# USB_Audio_for_Switch.net
KiCad netlist of a schematic drawn in EAGLE
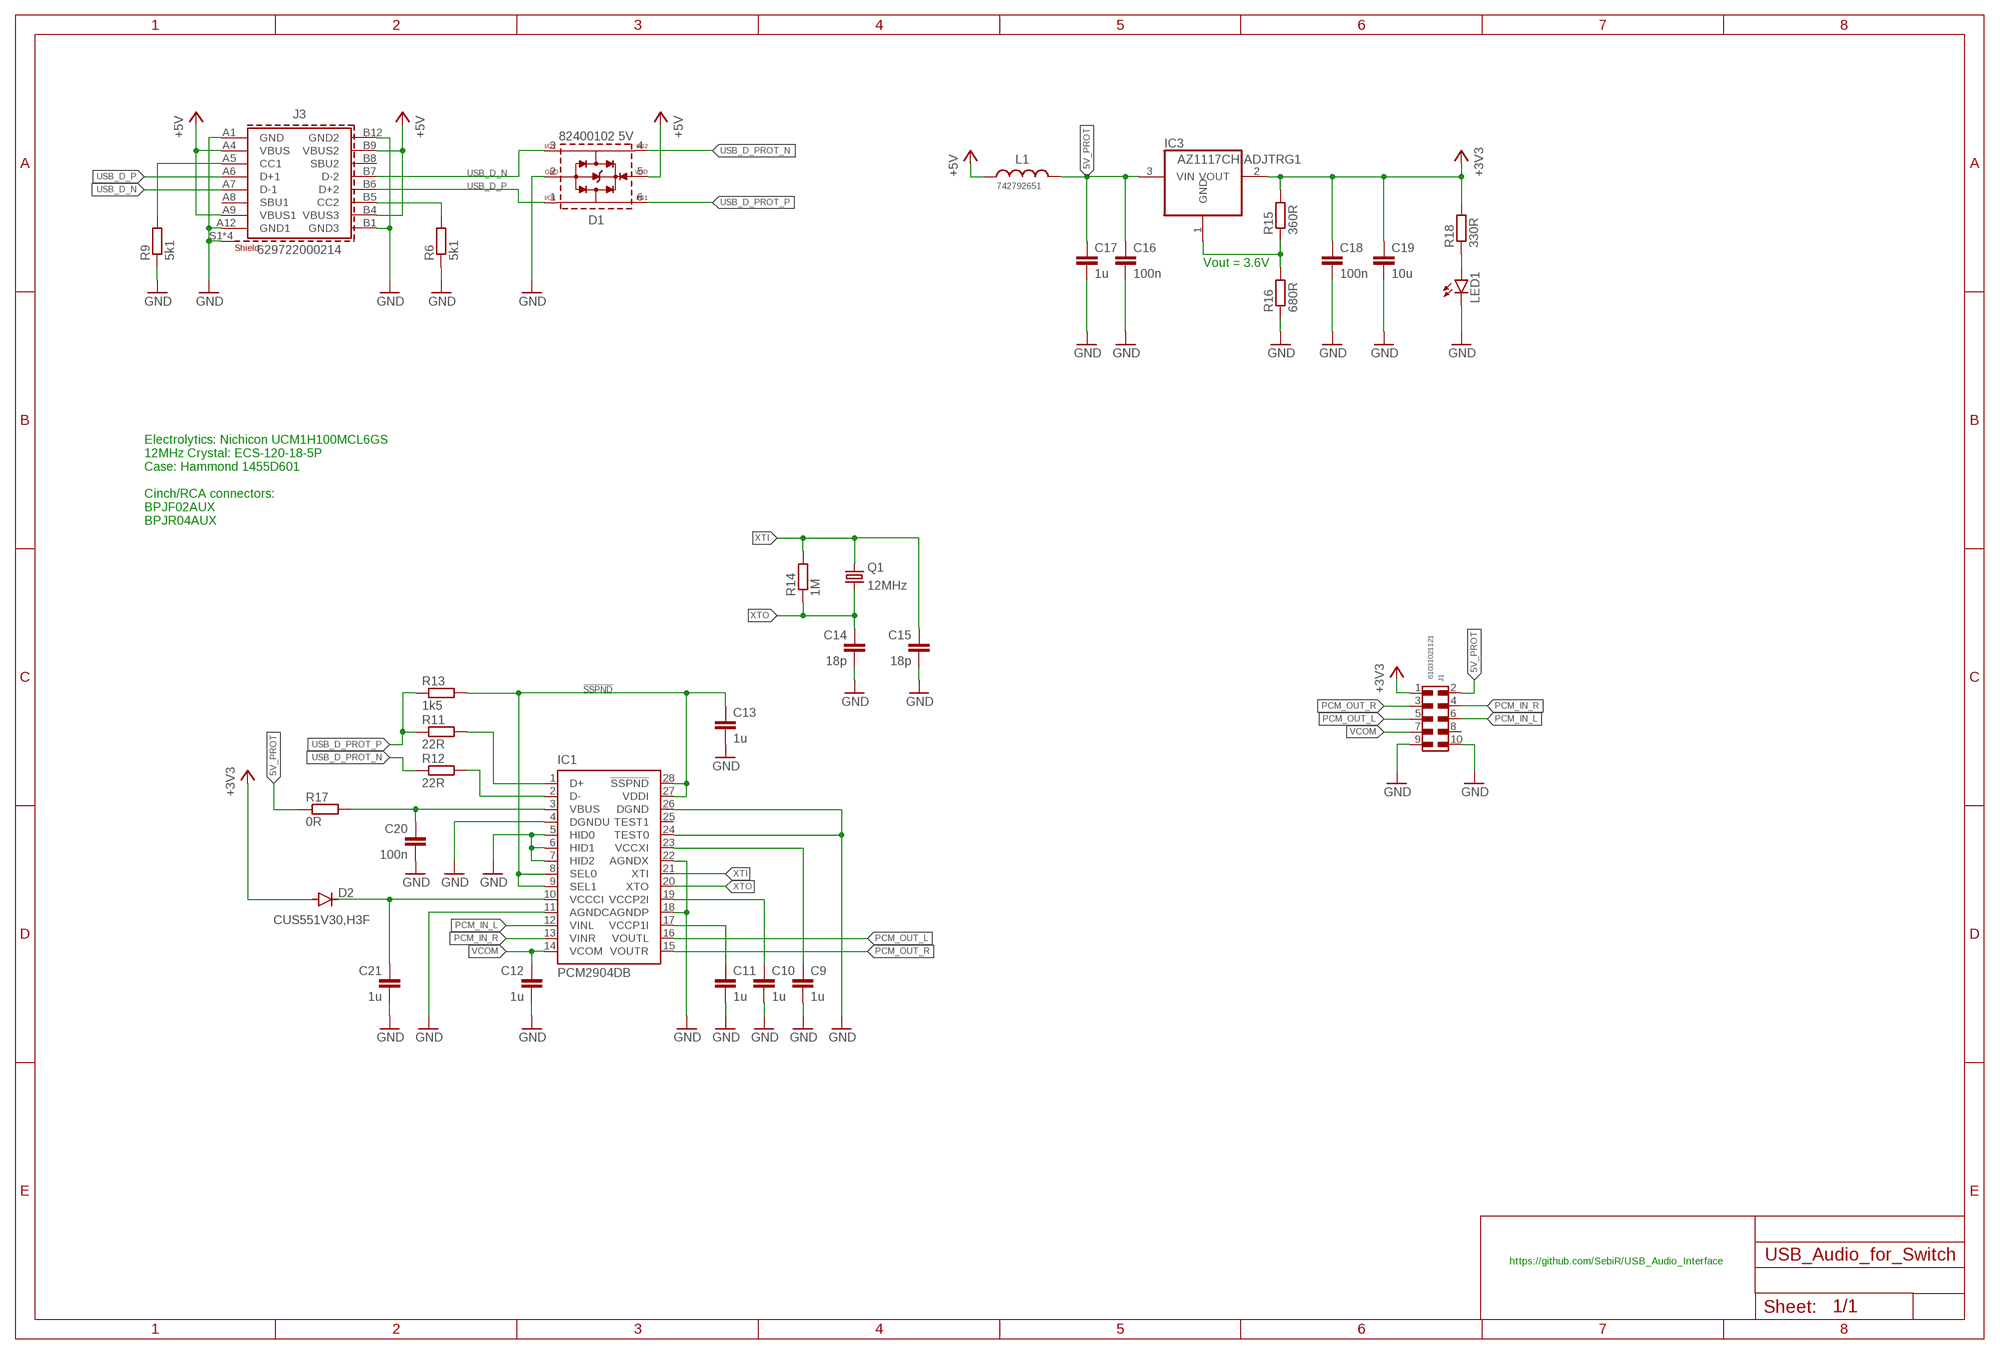
[diagram p0: schematic, sheet 1]

(export (version "E")
  (design (tool "Eeschema 10.0.6"))
  (components
    (comp (ref "C9")
      (value "1u")
      (footprint "eagle-import:C0603")
      (libsource (lib "eagle-import") (part "C-EUC0603"))
    )
    (comp (ref "C10")
      (value "1u")
      (footprint "eagle-import:C0603")
      (libsource (lib "eagle-import") (part "C-EUC0603"))
    )
    (comp (ref "C11")
      (value "1u")
      (footprint "eagle-import:C0603")
      (libsource (lib "eagle-import") (part "C-EUC0603"))
    )
    (comp (ref "C12")
      (value "1u")
      (footprint "eagle-import:C0603")
      (libsource (lib "eagle-import") (part "C-EUC0603"))
    )
    (comp (ref "C13")
      (value "1u")
      (footprint "eagle-import:C0603")
      (libsource (lib "eagle-import") (part "C-EUC0603"))
    )
    (comp (ref "C14")
      (value "18p")
      (footprint "eagle-import:C0603")
      (libsource (lib "eagle-import") (part "C-EUC0603"))
    )
    (comp (ref "C15")
      (value "18p")
      (footprint "eagle-import:C0603")
      (libsource (lib "eagle-import") (part "C-EUC0603"))
    )
    (comp (ref "C16")
      (value "100n")
      (footprint "eagle-import:C0603")
      (libsource (lib "eagle-import") (part "C-EUC0603"))
    )
    (comp (ref "C17")
      (value "1u")
      (footprint "eagle-import:C0603")
      (libsource (lib "eagle-import") (part "C-EUC0603"))
    )
    (comp (ref "C18")
      (value "100n")
      (footprint "eagle-import:C0603")
      (libsource (lib "eagle-import") (part "C-EUC0603"))
    )
    (comp (ref "C19")
      (value "10u")
      (footprint "eagle-import:C0603")
      (libsource (lib "eagle-import") (part "C-EUC0603"))
    )
    (comp (ref "C20")
      (value "100n")
      (footprint "eagle-import:C0603")
      (libsource (lib "eagle-import") (part "C-EUC0603"))
    )
    (comp (ref "C21")
      (value "1u")
      (footprint "eagle-import:C0603")
      (libsource (lib "eagle-import") (part "C-EUC0603"))
    )
    (comp (ref "D1")
      (value "82400102 5V")
      (footprint "eagle-import:WE-TVS_SOT23-6L")
      (libsource (lib "eagle-import") (part "WE-TVS-HS_SOT23-6L_82400102"))
    )
    (comp (ref "D2")
      (value "CUS551V30,H3F")
      (footprint "eagle-import:SOD323-R")
      (libsource (lib "eagle-import") (part "DIODE-SOD323-R"))
    )
    (comp (ref "IC1")
      (value "PCM2904DB")
      (footprint "eagle-import:SSOP28DB")
      (fields (field (name "MF") "TEXAS INSTRUMENT CONNECTORS"))
      (libsource (lib "eagle-import") (part "PCM2904DB"))
    )
    (comp (ref "IC3")
      (value "AZ1117CH-ADJTRG1")
      (footprint "eagle-import:SOT223")
      (fields (field (name "MPN") "REG1117"))
      (libsource (lib "eagle-import") (part "REG1117"))
    )
    (comp (ref "J1")
      (value "61031021121")
      (footprint "eagle-import:61031021121")
      (libsource (lib "eagle-import") (part "6103XX21121_61031021121"))
    )
    (comp (ref "J3")
      (value "629722000214")
      (footprint "eagle-import:629722000214")
      (libsource (lib "eagle-import") (part "629722000214"))
    )
    (comp (ref "L1")
      (value "742792651")
      (footprint "eagle-import:WE-CBF_0603_W2.6")
      (libsource (lib "eagle-import") (part "WE-CBF_0603_HC_742792651"))
    )
    (comp (ref "LED1")
      (value "LEDMICRO-SIDELED")
      (footprint "eagle-import:MICRO-SIDELED")
      (libsource (lib "eagle-import") (part "LEDMICRO-SIDELED"))
    )
    (comp (ref "Q1")
      (value "12MHz")
      (footprint "eagle-import:HC49UP")
      (libsource (lib "eagle-import") (part "CRYSTALHC49UP"))
    )
    (comp (ref "R6")
      (value "5k1")
      (footprint "eagle-import:R0603")
      (libsource (lib "eagle-import") (part "R-EU_R0603"))
    )
    (comp (ref "R9")
      (value "5k1")
      (footprint "eagle-import:R0603")
      (libsource (lib "eagle-import") (part "R-EU_R0603"))
    )
    (comp (ref "R11")
      (value "22R")
      (footprint "eagle-import:R0603")
      (libsource (lib "eagle-import") (part "R-EU_R0603"))
    )
    (comp (ref "R12")
      (value "22R")
      (footprint "eagle-import:R0603")
      (libsource (lib "eagle-import") (part "R-EU_R0603"))
    )
    (comp (ref "R13")
      (value "1k5")
      (footprint "eagle-import:R0603")
      (libsource (lib "eagle-import") (part "R-EU_R0603"))
    )
    (comp (ref "R14")
      (value "1M")
      (footprint "eagle-import:R0603")
      (libsource (lib "eagle-import") (part "R-EU_R0603"))
    )
    (comp (ref "R15")
      (value "360R")
      (footprint "eagle-import:R0603")
      (libsource (lib "eagle-import") (part "R-EU_R0603"))
    )
    (comp (ref "R16")
      (value "680R")
      (footprint "eagle-import:R0603")
      (libsource (lib "eagle-import") (part "R-EU_R0603"))
    )
    (comp (ref "R17")
      (value "0R")
      (footprint "eagle-import:R0603")
      (libsource (lib "eagle-import") (part "R-EU_R0603"))
    )
    (comp (ref "R18")
      (value "330R")
      (footprint "eagle-import:R0603")
      (libsource (lib "eagle-import") (part "R-EU_R0603"))
    )
  )
  (nets
    (net (code "1") (name "+3V3") (class "Default")
      (node (ref "C18") (pin "1") (pinfunction "1_1") (pintype "passive"))
      (node (ref "C19") (pin "1") (pinfunction "1_1") (pintype "passive"))
      (node (ref "D2") (pin "A") (pinfunction "A_A") (pintype "passive"))
      (node (ref "IC3") (pin "2") (pinfunction "VOUT_2") (pintype "output"))
      (node (ref "J1") (pin "1") (pinfunction "1_1") (pintype "passive"))
      (node (ref "R15") (pin "2") (pinfunction "2_2") (pintype "passive"))
      (node (ref "R18") (pin "2") (pinfunction "2_2") (pintype "passive"))
    )
    (net (code "2") (name "+5V") (class "Default")
      (node (ref "D1") (pin "5") (pinfunction "VDD_5") (pintype "passive"))
      (node (ref "J3") (pin "A4") (pinfunction "VBUS_A4") (pintype "passive"))
      (node (ref "J3") (pin "A9") (pinfunction "VBUS1_A9") (pintype "passive"))
      (node (ref "J3") (pin "B4") (pinfunction "VBUS3_B4") (pintype "passive"))
      (node (ref "J3") (pin "B9") (pinfunction "VBUS2_B9") (pintype "passive"))
      (node (ref "L1") (pin "1") (pinfunction "1_1") (pintype "passive"))
    )
    (net (code "3") (name "/~{SSPND}") (class "Default")
      (node (ref "C13") (pin "1") (pinfunction "1_1") (pintype "passive"))
      (node (ref "IC1") (pin "27") (pinfunction "VDDI_27") (pintype "power_in"))
      (node (ref "IC1") (pin "28") (pinfunction "~{SSPND}_28") (pintype "output"))
      (node (ref "IC1") (pin "8") (pinfunction "SEL0_8") (pintype "input"))
      (node (ref "IC1") (pin "9") (pinfunction "SEL1_9") (pintype "input"))
      (node (ref "R13") (pin "2") (pinfunction "2_2") (pintype "passive"))
    )
    (net (code "4") (name "5V_PROT") (class "Default")
      (node (ref "C16") (pin "1") (pinfunction "1_1") (pintype "passive"))
      (node (ref "C17") (pin "1") (pinfunction "1_1") (pintype "passive"))
      (node (ref "IC3") (pin "3") (pinfunction "VIN_3") (pintype "input"))
      (node (ref "J1") (pin "2") (pinfunction "2_2") (pintype "passive"))
      (node (ref "L1") (pin "2") (pinfunction "2_2") (pintype "passive"))
      (node (ref "R17") (pin "1") (pinfunction "1_1") (pintype "passive"))
    )
    (net (code "5") (name "GND") (class "Default")
      (node (ref "C10") (pin "2") (pinfunction "2_2") (pintype "passive"))
      (node (ref "C11") (pin "2") (pinfunction "2_2") (pintype "passive"))
      (node (ref "C12") (pin "2") (pinfunction "2_2") (pintype "passive"))
      (node (ref "C13") (pin "2") (pinfunction "2_2") (pintype "passive"))
      (node (ref "C14") (pin "2") (pinfunction "2_2") (pintype "passive"))
      (node (ref "C15") (pin "2") (pinfunction "2_2") (pintype "passive"))
      (node (ref "C16") (pin "2") (pinfunction "2_2") (pintype "passive"))
      (node (ref "C17") (pin "2") (pinfunction "2_2") (pintype "passive"))
      (node (ref "C18") (pin "2") (pinfunction "2_2") (pintype "passive"))
      (node (ref "C19") (pin "2") (pinfunction "2_2") (pintype "passive"))
      (node (ref "C20") (pin "2") (pinfunction "2_2") (pintype "passive"))
      (node (ref "C21") (pin "2") (pinfunction "2_2") (pintype "passive"))
      (node (ref "C9") (pin "2") (pinfunction "2_2") (pintype "passive"))
      (node (ref "D1") (pin "2") (pinfunction "GND_2") (pintype "passive"))
      (node (ref "IC1") (pin "11") (pinfunction "AGNDC_11") (pintype "power_in"))
      (node (ref "IC1") (pin "18") (pinfunction "AGNDP_18") (pintype "power_in"))
      (node (ref "IC1") (pin "22") (pinfunction "AGNDX_22") (pintype "power_in"))
      (node (ref "IC1") (pin "24") (pinfunction "TEST0_24") (pintype "input"))
      (node (ref "IC1") (pin "26") (pinfunction "DGND_26") (pintype "power_in"))
      (node (ref "IC1") (pin "4") (pinfunction "DGNDU_4") (pintype "power_in"))
      (node (ref "IC1") (pin "5") (pinfunction "HID0_5") (pintype "input"))
      (node (ref "IC1") (pin "6") (pinfunction "HID1_6") (pintype "input"))
      (node (ref "IC1") (pin "7") (pinfunction "HID2_7") (pintype "input"))
      (node (ref "J1") (pin "10") (pinfunction "10_10") (pintype "passive"))
      (node (ref "J1") (pin "9") (pinfunction "9_9") (pintype "passive"))
      (node (ref "J3") (pin "A1") (pinfunction "GND_A1") (pintype "passive"))
      (node (ref "J3") (pin "A12") (pinfunction "GND1_A12") (pintype "passive"))
      (node (ref "J3") (pin "B1") (pinfunction "GND3_B1") (pintype "passive"))
      (node (ref "J3") (pin "B12") (pinfunction "GND2_B12") (pintype "passive"))
      (node (ref "J3") (pin "S1") (pinfunction "SHIELD_S1") (pintype "passive"))
      (node (ref "J3") (pin "S2") (pinfunction "SHIELD_S2") (pintype "passive"))
      (node (ref "J3") (pin "S3") (pinfunction "SHIELD_S3") (pintype "passive"))
      (node (ref "J3") (pin "S4") (pinfunction "SHIELD_S4") (pintype "passive"))
      (node (ref "LED1") (pin "C") (pinfunction "C_C") (pintype "passive"))
      (node (ref "R16") (pin "1") (pinfunction "1_1") (pintype "passive"))
      (node (ref "R6") (pin "1") (pinfunction "1_1") (pintype "passive"))
      (node (ref "R9") (pin "1") (pinfunction "1_1") (pintype "passive"))
    )
    (net (code "6") (name "Net-(IC1-D+)") (class "Default")
      (node (ref "IC1") (pin "1") (pinfunction "D+_1") (pintype "bidirectional"))
      (node (ref "R11") (pin "2") (pinfunction "2_2") (pintype "passive"))
    )
    (net (code "7") (name "Net-(IC1-D-)") (class "Default")
      (node (ref "IC1") (pin "2") (pinfunction "D-_2") (pintype "bidirectional"))
      (node (ref "R12") (pin "2") (pinfunction "2_2") (pintype "passive"))
    )
    (net (code "8") (name "Net-(IC1-VBUS)") (class "Default")
      (node (ref "C20") (pin "1") (pinfunction "1_1") (pintype "passive"))
      (node (ref "IC1") (pin "3") (pinfunction "VBUS_3") (pintype "power_in"))
      (node (ref "R17") (pin "2") (pinfunction "2_2") (pintype "passive"))
    )
    (net (code "9") (name "Net-(IC1-VCCCI)") (class "Default")
      (node (ref "C21") (pin "1") (pinfunction "1_1") (pintype "passive"))
      (node (ref "D2") (pin "C") (pinfunction "C_C") (pintype "passive"))
      (node (ref "IC1") (pin "10") (pinfunction "VCCCI_10") (pintype "power_in"))
    )
    (net (code "10") (name "Net-(IC1-VCCP1I)") (class "Default")
      (node (ref "C11") (pin "1") (pinfunction "1_1") (pintype "passive"))
      (node (ref "IC1") (pin "17") (pinfunction "VCCP1I_17") (pintype "input"))
    )
    (net (code "11") (name "Net-(IC1-VCCP2I)") (class "Default")
      (node (ref "C10") (pin "1") (pinfunction "1_1") (pintype "passive"))
      (node (ref "IC1") (pin "19") (pinfunction "VCCP2I_19") (pintype "power_in"))
    )
    (net (code "12") (name "Net-(IC1-VCCXI)") (class "Default")
      (node (ref "C9") (pin "1") (pinfunction "1_1") (pintype "passive"))
      (node (ref "IC1") (pin "23") (pinfunction "VCCXI_23") (pintype "power_in"))
    )
    (net (code "13") (name "Net-(IC3-GND)") (class "Default")
      (node (ref "IC3") (pin "1") (pinfunction "GND_1") (pintype "power_in"))
      (node (ref "R15") (pin "1") (pinfunction "1_1") (pintype "passive"))
      (node (ref "R16") (pin "2") (pinfunction "2_2") (pintype "passive"))
    )
    (net (code "14") (name "Net-(J3-CC1)") (class "Default")
      (node (ref "J3") (pin "A5") (pinfunction "CC1_A5") (pintype "passive"))
      (node (ref "R9") (pin "2") (pinfunction "2_2") (pintype "passive"))
    )
    (net (code "15") (name "Net-(J3-CC2)") (class "Default")
      (node (ref "J3") (pin "B5") (pinfunction "CC2_B5") (pintype "passive"))
      (node (ref "R6") (pin "2") (pinfunction "2_2") (pintype "passive"))
    )
    (net (code "16") (name "Net-(LED1-PadA)") (class "Default")
      (node (ref "LED1") (pin "A") (pinfunction "A_A") (pintype "passive"))
      (node (ref "R18") (pin "1") (pinfunction "1_1") (pintype "passive"))
    )
    (net (code "17") (name "PCM_IN_L") (class "Default")
      (node (ref "IC1") (pin "12") (pinfunction "VINL_12") (pintype "input"))
      (node (ref "J1") (pin "6") (pinfunction "6_6") (pintype "passive"))
    )
    (net (code "18") (name "PCM_IN_R") (class "Default")
      (node (ref "IC1") (pin "13") (pinfunction "VINR_13") (pintype "input"))
      (node (ref "J1") (pin "4") (pinfunction "4_4") (pintype "passive"))
    )
    (net (code "19") (name "PCM_OUT_L") (class "Default")
      (node (ref "IC1") (pin "16") (pinfunction "VOUTL_16") (pintype "output"))
      (node (ref "J1") (pin "5") (pinfunction "5_5") (pintype "passive"))
    )
    (net (code "20") (name "PCM_OUT_R") (class "Default")
      (node (ref "IC1") (pin "15") (pinfunction "VOUTR_15") (pintype "output"))
      (node (ref "J1") (pin "3") (pinfunction "3_3") (pintype "passive"))
    )
    (net (code "21") (name "USB_D_N") (class "Default")
      (node (ref "D1") (pin "3") (pinfunction "I/O2_3") (pintype "passive"))
      (node (ref "J3") (pin "A7") (pinfunction "D-1_A7") (pintype "passive"))
      (node (ref "J3") (pin "B7") (pinfunction "D-2_B7") (pintype "passive"))
    )
    (net (code "22") (name "USB_D_P") (class "Default")
      (node (ref "D1") (pin "1") (pinfunction "I/O1_1") (pintype "passive"))
      (node (ref "J3") (pin "A6") (pinfunction "D+1_A6") (pintype "passive"))
      (node (ref "J3") (pin "B6") (pinfunction "D+2_B6") (pintype "passive"))
    )
    (net (code "23") (name "USB_D_PROT_N") (class "Default")
      (node (ref "D1") (pin "4") (pinfunction "I/O4_4") (pintype "passive"))
      (node (ref "R12") (pin "1") (pinfunction "1_1") (pintype "passive"))
    )
    (net (code "24") (name "USB_D_PROT_P") (class "Default")
      (node (ref "D1") (pin "6") (pinfunction "I/O3_6") (pintype "passive"))
      (node (ref "R11") (pin "1") (pinfunction "1_1") (pintype "passive"))
      (node (ref "R13") (pin "1") (pinfunction "1_1") (pintype "passive"))
    )
    (net (code "25") (name "VCOM") (class "Default")
      (node (ref "C12") (pin "1") (pinfunction "1_1") (pintype "passive"))
      (node (ref "IC1") (pin "14") (pinfunction "VCOM_14") (pintype "power_in"))
      (node (ref "J1") (pin "7") (pinfunction "7_7") (pintype "passive"))
    )
    (net (code "26") (name "XTI") (class "Default")
      (node (ref "C15") (pin "1") (pinfunction "1_1") (pintype "passive"))
      (node (ref "IC1") (pin "21") (pinfunction "XTI_21") (pintype "input"))
      (node (ref "Q1") (pin "2") (pinfunction "2_2") (pintype "passive"))
      (node (ref "R14") (pin "2") (pinfunction "2_2") (pintype "passive"))
    )
    (net (code "27") (name "XTO") (class "Default")
      (node (ref "C14") (pin "1") (pinfunction "1_1") (pintype "passive"))
      (node (ref "IC1") (pin "20") (pinfunction "XTO_20") (pintype "output"))
      (node (ref "Q1") (pin "1") (pinfunction "1_1") (pintype "passive"))
      (node (ref "R14") (pin "1") (pinfunction "1_1") (pintype "passive"))
    )
    (net (code "28") (name "unconnected-(IC1-TEST1-Pad25)") (class "Default")
      (node (ref "IC1") (pin "25") (pinfunction "TEST1_25") (pintype "output"))
    )
    (net (code "29") (name "unconnected-(J1-Pad8)") (class "Default")
      (node (ref "J1") (pin "8") (pinfunction "8_8") (pintype "passive"))
    )
    (net (code "30") (name "unconnected-(J3-SBU1-PadA8)") (class "Default")
      (node (ref "J3") (pin "A8") (pinfunction "SBU1_A8") (pintype "passive"))
    )
    (net (code "31") (name "unconnected-(J3-SBU2-PadB8)") (class "Default")
      (node (ref "J3") (pin "B8") (pinfunction "SBU2_B8") (pintype "passive"))
    )
  )
)
